# Power_Supply.net
KiCad netlist of a schematic drawn in Altium Designer
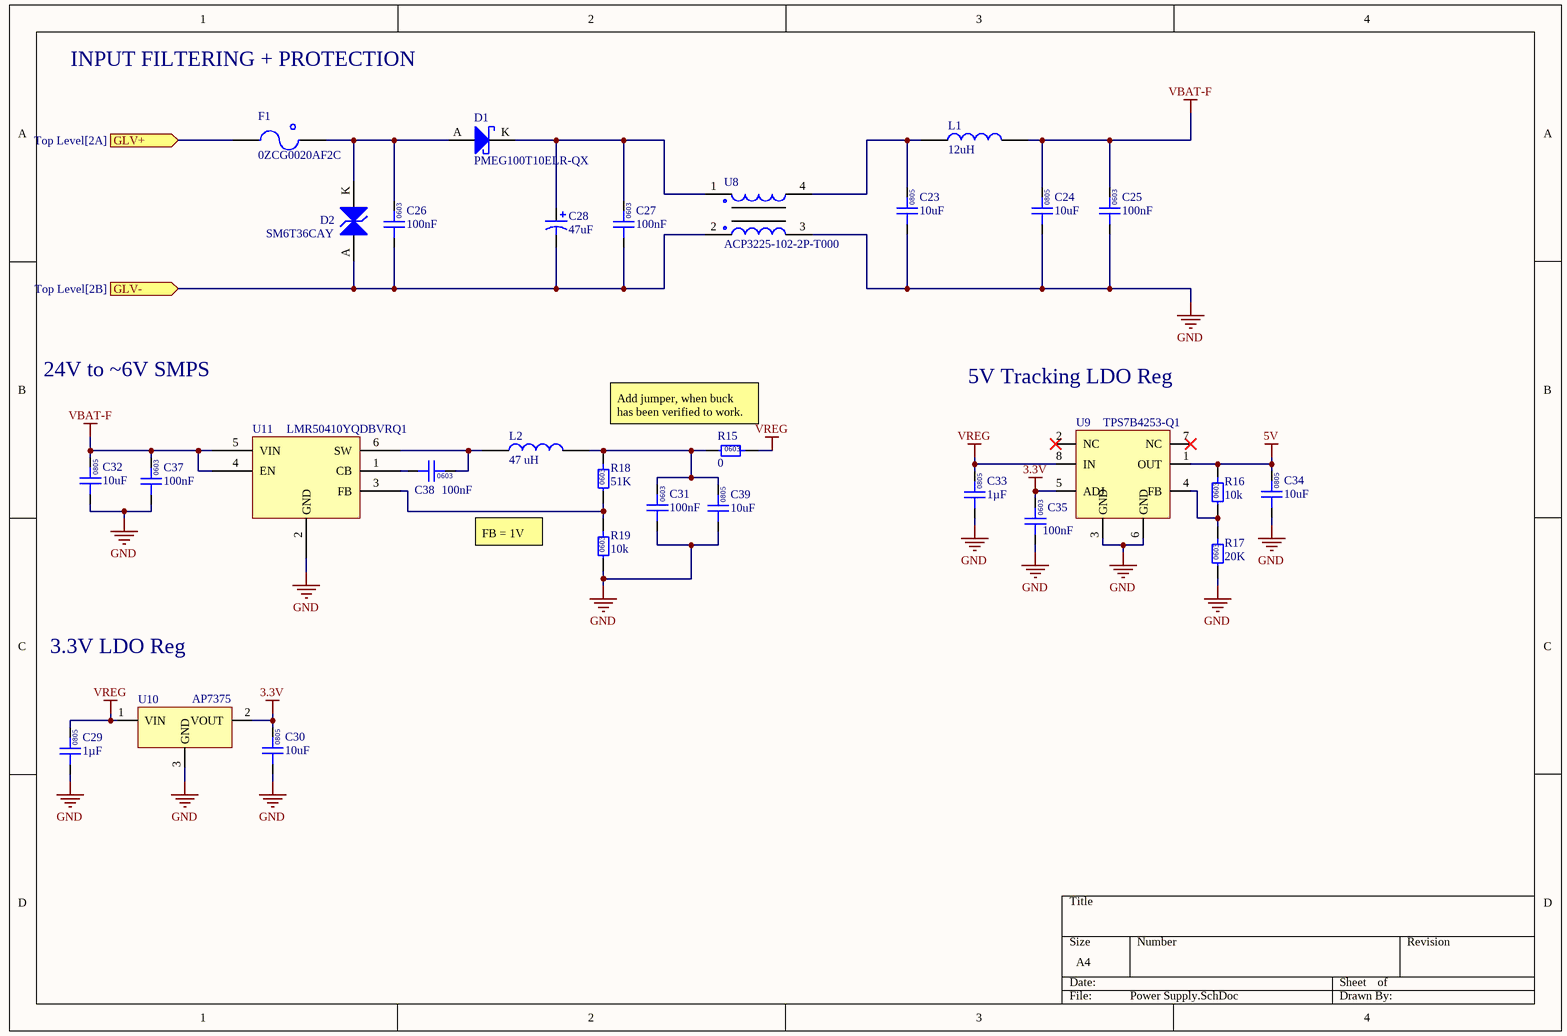
[diagram p0: Power Supply.SchDoc]

(export (version "E")
  (design (tool "Eeschema 10.0.6"))
  (components
    (comp (ref "C23")
      (value "10uF")
      (footprint "0805")
      (fields
        (field (name "PART NUMBER") "GRM21BR6YA106KE43L")
        (field (name "MANUFACTURER") "muRata")
        (field (name "TOLERANCE") "10%")
      )
      (libsource (lib "ts_standard_library") (part "Capacitor 0805"))
    )
    (comp (ref "C24")
      (value "10uF")
      (footprint "0805")
      (fields
        (field (name "PART NUMBER") "GRM21BR6YA106KE43L")
        (field (name "MANUFACTURER") "muRata")
        (field (name "TOLERANCE") "10%")
      )
      (libsource (lib "ts_standard_library") (part "Capacitor 0805"))
    )
    (comp (ref "C25")
      (value "100nF")
      (footprint "0603")
      (fields
        (field (name "PART NUMBER") "GCM188L81H104KA57D")
        (field (name "MANUFACTURER") "muRata")
        (field (name "TOLERANCE") "±10%")
      )
      (libsource (lib "ts_standard_library") (part "Capacitor 0603"))
    )
    (comp (ref "C26")
      (value "100nF")
      (footprint "0603")
      (fields
        (field (name "PART NUMBER") "GCM188L81H104KA57D")
        (field (name "MANUFACTURER") "muRata")
        (field (name "TOLERANCE") "±10%")
      )
      (libsource (lib "ts_standard_library") (part "Capacitor 0603"))
    )
    (comp (ref "C27")
      (value "100nF")
      (footprint "0603")
      (fields
        (field (name "PART NUMBER") "GCM188L81H104KA57D")
        (field (name "MANUFACTURER") "muRata")
        (field (name "TOLERANCE") "±10%")
      )
      (libsource (lib "ts_standard_library") (part "Capacitor 0603"))
    )
    (comp (ref "C28")
      (value "47uF")
      (footprint "CHEMI-CON ELCO")
      (fields (field (name "PART NUMBER") "HHXA350ARA470MF61G"))
      (libsource (lib "ts_standard_library") (part "Capacitor (Polarised)"))
    )
    (comp (ref "C29")
      (value "1µF")
      (footprint "0805")
      (fields
        (field (name "PART NUMBER") "GCM21BR71H105KA03L")
        (field (name "MANUFACTURER") "muRata")
        (field (name "TOLERANCE") "±10%")
      )
      (libsource (lib "ts_standard_library") (part "Capacitor 0805"))
    )
    (comp (ref "C30")
      (value "10uF")
      (footprint "0805")
      (fields
        (field (name "PART NUMBER") "GRM21BR6YA106KE43L")
        (field (name "MANUFACTURER") "muRata")
        (field (name "TOLERANCE") "10%")
      )
      (libsource (lib "ts_standard_library") (part "Capacitor 0805"))
    )
    (comp (ref "C31")
      (value "100nF")
      (footprint "0603")
      (fields
        (field (name "PART NUMBER") "GCM188L81H104KA57D")
        (field (name "MANUFACTURER") "muRata")
        (field (name "TOLERANCE") "±10%")
      )
      (libsource (lib "ts_standard_library") (part "Capacitor 0603"))
    )
    (comp (ref "C32")
      (value "10uF")
      (footprint "0805")
      (fields
        (field (name "PART NUMBER") "GRM21BR6YA106KE43L")
        (field (name "MANUFACTURER") "muRata")
        (field (name "TOLERANCE") "10%")
      )
      (libsource (lib "ts_standard_library") (part "Capacitor 0805"))
    )
    (comp (ref "C33")
      (value "1µF")
      (footprint "0805")
      (fields
        (field (name "PART NUMBER") "GCM21BR71H105KA03L")
        (field (name "MANUFACTURER") "muRata")
        (field (name "TOLERANCE") "±10%")
      )
      (libsource (lib "ts_standard_library") (part "Capacitor 0805"))
    )
    (comp (ref "C34")
      (value "10uF")
      (footprint "0805")
      (fields
        (field (name "PART NUMBER") "GRM21BR6YA106KE43L")
        (field (name "MANUFACTURER") "muRata")
        (field (name "TOLERANCE") "10%")
      )
      (libsource (lib "ts_standard_library") (part "Capacitor 0805"))
    )
    (comp (ref "C35")
      (value "100nF")
      (footprint "0603")
      (fields
        (field (name "PART NUMBER") "GCM188L81H104KA57D")
        (field (name "MANUFACTURER") "muRata")
        (field (name "TOLERANCE") "±10%")
      )
      (libsource (lib "ts_standard_library") (part "Capacitor 0603"))
    )
    (comp (ref "C37")
      (value "100nF")
      (footprint "0603")
      (fields
        (field (name "PART NUMBER") "GCM188L81H104KA57D")
        (field (name "MANUFACTURER") "muRata")
        (field (name "TOLERANCE") "±10%")
      )
      (libsource (lib "ts_standard_library") (part "Capacitor 0603"))
    )
    (comp (ref "C38")
      (value "100nF")
      (footprint "0603")
      (fields
        (field (name "PART NUMBER") "GCM188L81H104KA57D")
        (field (name "MANUFACTURER") "muRata")
        (field (name "TOLERANCE") "±10%")
      )
      (libsource (lib "ts_standard_library") (part "Capacitor 0603"))
    )
    (comp (ref "C39")
      (value "10uF")
      (footprint "0805")
      (fields
        (field (name "PART NUMBER") "GRM21BR6YA106KE43L")
        (field (name "MANUFACTURER") "muRata")
        (field (name "TOLERANCE") "10%")
      )
      (libsource (lib "ts_standard_library") (part "Capacitor 0805"))
    )
    (comp (ref "D1")
      (value "PMEG100T10ELR-QX")
      (footprint "NXP SOD123W")
      (fields
        (field (name "MANUFACTURER") "Nexperia USA Inc.")
        (field (name "DIGIKEY PART NUMBER") "1727-PMEG100T10ELR-QXCT-ND")
      )
      (libsource (lib "ts_standard_library") (part "Diode (Schottky)"))
    )
    (comp (ref "D2")
      (value "SM6T36CAY")
      (footprint "ST SMB DIODE")
      (fields
        (field (name "MANUFACTURER") "STMicroelectronics")
        (field (name "DIGIKEY PART NUMBER") "497-10804-1-ND")
      )
      (libsource (lib "ts_standard_library") (part "TVS (Bidirectional)"))
    )
    (comp (ref "F1")
      (value "0ZCG0020AF2C")
      (footprint "1812 (PPTC FUSE)")
      (description "PTC RESET FUSE 60V 200MA 1812")
      (fields
        (field (name "MANUFACTURER") "Bel Fuse Inc.")
        (field (name "DIGIKEY PART NUMBER") "507-1757-1-ND")
      )
      (libsource (lib "ts_standard_library") (part "PTC Fuse"))
    )
    (comp (ref "L1")
      (value "12uH")
      (footprint "1812")
      (fields
        (field (name "PART NUMBER") "RLS-126")
        (field (name "MANUFACTURER") "Recom")
        (field (name "TOLERANCE") "0.2")
      )
      (libsource (lib "ts_standard_library") (part "Inductor"))
    )
    (comp (ref "L2")
      (value "47 uH")
      (footprint "SRN8040TA")
      (fields
        (field (name "PART NUMBER") "SRN8040TA-470M")
        (field (name "MANUFACTURER") "Bourns")
        (field (name "TOLERANCE") "0.2")
      )
      (libsource (lib "ts_standard_library") (part "Inductor"))
    )
    (comp (ref "R15")
      (value "0")
      (footprint "0603")
      (fields
        (field (name "PART NUMBER") "RC0603JR-070RL")
        (field (name "MANUFACTURER") "YAGEO")
        (field (name "TOLERANCE") "0.01")
      )
      (libsource (lib "ts_standard_library") (part "Resistor 0603"))
    )
    (comp (ref "R16")
      (value "10k")
      (footprint "0603")
      (fields
        (field (name "PART NUMBER") "RC0603FR-0710KL")
        (field (name "MANUFACTURER") "YAGEO")
        (field (name "TOLERANCE") "0.01")
      )
      (libsource (lib "ts_standard_library") (part "Resistor 0603"))
    )
    (comp (ref "R17")
      (value "20K")
      (footprint "0603")
      (fields
        (field (name "PART NUMBER") "RC0603FR-0720KL")
        (field (name "MANUFACTURER") "YAGEO")
        (field (name "TOLERANCE") "0.01")
      )
      (libsource (lib "ts_standard_library") (part "Resistor 0603"))
    )
    (comp (ref "R18")
      (value "51K")
      (footprint "0603")
      (fields
        (field (name "PART NUMBER") "RC0603JR-0751KL")
        (field (name "MANUFACTURER") "YAGEO")
        (field (name "TOLERANCE") "0.01")
      )
      (libsource (lib "ts_standard_library") (part "Resistor 0603"))
    )
    (comp (ref "R19")
      (value "10k")
      (footprint "0603")
      (fields
        (field (name "PART NUMBER") "RC0603FR-0710KL")
        (field (name "MANUFACTURER") "YAGEO")
        (field (name "TOLERANCE") "0.01")
      )
      (libsource (lib "ts_standard_library") (part "Resistor 0603"))
    )
    (comp (ref "U8")
      (value "ACP3225-102-2P-T000")
      (footprint "ACP3225")
      (fields
        (field (name "MANUFACTURER") "TDK Corporation")
        (field (name "TOLERANCE") "0.25")
        (field (name "DIGIKEY PART NUMBER") "445-8637-1-ND")
      )
      (libsource (lib "ts_standard_library") (part "CM Choke 2"))
    )
    (comp (ref "U9")
      (value "TPS7B4253-Q1")
      (footprint "TI 8-PowerSOIC")
      (description "IC REG LIN POS ADJ 300MA 8SO")
      (fields
        (field (name "MANUFACTURER") "Texas Instruments")
        (field (name "DIGIKEY PART NUMBER") "296-43781-1-ND")
      )
      (libsource (lib "ts_standard_library") (part "TPS7B4253-Q1"))
    )
    (comp (ref "U10")
      (value "AP7375")
      (footprint "DI SOT-23-3")
      (description "IC REG LIN 3.3V 300MA SOT23-3")
      (fields
        (field (name "PART NUMBER") "AP7375-33SA-7")
        (field (name "MANUFACTURER") "Diodes Incorporated")
      )
      (libsource (lib "ts_standard_library") (part "AP7375"))
    )
    (comp (ref "U11")
      (value "LMR50410YQDBVRQ1")
      (footprint "TI SOT-23-6")
      (description "IC REG BUCK ADJ 1A SOT23-6")
      (fields
        (field (name "MANUFACTURER") "Texas Instruments")
        (field (name "DIGIKEY PART NUMBER") "296-LMR50410YQDBVRQ1CT-ND")
      )
      (libsource (lib "ts_standard_library") (part "LMR50410-Q1"))
    )
  )
  (nets
    (net (code "1") (name "/GLV+") (class "Default")
      (node (ref "F1") (pin "1") (pinfunction "1_1") (pintype "passive"))
    )
    (net (code "2") (name "/GLV-") (class "Default")
      (node (ref "C26") (pin "1") (pinfunction "1_1") (pintype "passive"))
      (node (ref "C27") (pin "1") (pinfunction "1_1") (pintype "passive"))
      (node (ref "C28") (pin "1") (pinfunction "1_1") (pintype "passive"))
      (node (ref "D2") (pin "A") (pinfunction "A_A") (pintype "passive"))
      (node (ref "U8") (pin "2") (pinfunction "2_2") (pintype "passive"))
    )
    (net (code "3") (name "3.3V") (class "Default")
      (node (ref "C30") (pin "2") (pinfunction "2_2") (pintype "passive"))
      (node (ref "C35") (pin "2") (pinfunction "2_2") (pintype "passive"))
      (node (ref "U10") (pin "2") (pinfunction "VOUT_2") (pintype "passive"))
      (node (ref "U9") (pin "5") (pinfunction "ADJ_5") (pintype "passive"))
    )
    (net (code "4") (name "5V") (class "Default")
      (node (ref "C34") (pin "2") (pinfunction "2_2") (pintype "passive"))
      (node (ref "R16") (pin "2") (pinfunction "2_2") (pintype "passive"))
      (node (ref "U9") (pin "1") (pinfunction "OUT_1") (pintype "passive"))
    )
    (net (code "5") (name "GND") (class "Default")
      (node (ref "C23") (pin "1") (pinfunction "1_1") (pintype "passive"))
      (node (ref "C24") (pin "1") (pinfunction "1_1") (pintype "passive"))
      (node (ref "C25") (pin "1") (pinfunction "1_1") (pintype "passive"))
      (node (ref "C29") (pin "1") (pinfunction "1_1") (pintype "passive"))
      (node (ref "C30") (pin "1") (pinfunction "1_1") (pintype "passive"))
      (node (ref "C31") (pin "1") (pinfunction "1_1") (pintype "passive"))
      (node (ref "C32") (pin "1") (pinfunction "1_1") (pintype "passive"))
      (node (ref "C33") (pin "1") (pinfunction "1_1") (pintype "passive"))
      (node (ref "C34") (pin "1") (pinfunction "1_1") (pintype "passive"))
      (node (ref "C35") (pin "1") (pinfunction "1_1") (pintype "passive"))
      (node (ref "C37") (pin "1") (pinfunction "1_1") (pintype "passive"))
      (node (ref "C39") (pin "1") (pinfunction "1_1") (pintype "passive"))
      (node (ref "R17") (pin "1") (pinfunction "1_1") (pintype "passive"))
      (node (ref "R19") (pin "1") (pinfunction "1_1") (pintype "passive"))
      (node (ref "U10") (pin "3") (pinfunction "GND_3") (pintype "passive"))
      (node (ref "U11") (pin "2") (pinfunction "GND_2") (pintype "passive"))
      (node (ref "U8") (pin "3") (pinfunction "3_3") (pintype "power_in"))
      (node (ref "U9") (pin "3") (pinfunction "GND_3") (pintype "passive"))
      (node (ref "U9") (pin "6") (pinfunction "GND_6") (pintype "passive"))
    )
    (net (code "6") (name "Net-(C23-Pad2)") (class "Default")
      (node (ref "C23") (pin "2") (pinfunction "2_2") (pintype "passive"))
      (node (ref "L1") (pin "2") (pinfunction "2_2") (pintype "passive"))
      (node (ref "U8") (pin "4") (pinfunction "4_4") (pintype "passive"))
    )
    (net (code "7") (name "Net-(C26-Pad2)") (class "Default")
      (node (ref "C26") (pin "2") (pinfunction "2_2") (pintype "passive"))
      (node (ref "D1") (pin "A") (pinfunction "A_A") (pintype "passive"))
      (node (ref "D2") (pin "K") (pinfunction "K_K") (pintype "passive"))
      (node (ref "F1") (pin "2") (pinfunction "2_2") (pintype "passive"))
    )
    (net (code "8") (name "Net-(C27-Pad2)") (class "Default")
      (node (ref "C27") (pin "2") (pinfunction "2_2") (pintype "passive"))
      (node (ref "C28") (pin "2") (pinfunction "2_2") (pintype "passive"))
      (node (ref "D1") (pin "K") (pinfunction "K_K") (pintype "passive"))
      (node (ref "U8") (pin "1") (pinfunction "1_1") (pintype "passive"))
    )
    (net (code "9") (name "Net-(C31-Pad2)") (class "Default")
      (node (ref "C31") (pin "2") (pinfunction "2_2") (pintype "passive"))
      (node (ref "C39") (pin "2") (pinfunction "2_2") (pintype "passive"))
      (node (ref "L2") (pin "1") (pinfunction "1_1") (pintype "passive"))
      (node (ref "R15") (pin "1") (pinfunction "1_1") (pintype "passive"))
      (node (ref "R18") (pin "2") (pinfunction "2_2") (pintype "passive"))
    )
    (net (code "10") (name "Net-(U9-FB)") (class "Default")
      (node (ref "R16") (pin "1") (pinfunction "1_1") (pintype "passive"))
      (node (ref "R17") (pin "2") (pinfunction "2_2") (pintype "passive"))
      (node (ref "U9") (pin "4") (pinfunction "FB_4") (pintype "passive"))
    )
    (net (code "11") (name "Net-(U11-CB)") (class "Default")
      (node (ref "C38") (pin "1") (pinfunction "1_1") (pintype "passive"))
      (node (ref "U11") (pin "1") (pinfunction "CB_1") (pintype "passive"))
    )
    (net (code "12") (name "Net-(U11-FB)") (class "Default")
      (node (ref "R18") (pin "1") (pinfunction "1_1") (pintype "passive"))
      (node (ref "R19") (pin "2") (pinfunction "2_2") (pintype "passive"))
      (node (ref "U11") (pin "3") (pinfunction "FB_3") (pintype "passive"))
    )
    (net (code "13") (name "Net-(U11-SW)") (class "Default")
      (node (ref "C38") (pin "2") (pinfunction "2_2") (pintype "passive"))
      (node (ref "L2") (pin "2") (pinfunction "2_2") (pintype "passive"))
      (node (ref "U11") (pin "6") (pinfunction "SW_6") (pintype "passive"))
    )
    (net (code "14") (name "VBAT-F") (class "Default")
      (node (ref "C24") (pin "2") (pinfunction "2_2") (pintype "passive"))
      (node (ref "C25") (pin "2") (pinfunction "2_2") (pintype "passive"))
      (node (ref "C32") (pin "2") (pinfunction "2_2") (pintype "passive"))
      (node (ref "C37") (pin "2") (pinfunction "2_2") (pintype "passive"))
      (node (ref "L1") (pin "1") (pinfunction "1_1") (pintype "passive"))
      (node (ref "U11") (pin "4") (pinfunction "EN_4") (pintype "passive"))
      (node (ref "U11") (pin "5") (pinfunction "VIN_5") (pintype "passive"))
    )
    (net (code "15") (name "VREG") (class "Default")
      (node (ref "C29") (pin "2") (pinfunction "2_2") (pintype "passive"))
      (node (ref "C33") (pin "2") (pinfunction "2_2") (pintype "passive"))
      (node (ref "R15") (pin "2") (pinfunction "2_2") (pintype "passive"))
      (node (ref "U10") (pin "1") (pinfunction "VIN_1") (pintype "passive"))
      (node (ref "U9") (pin "8") (pinfunction "IN_8") (pintype "passive"))
    )
    (net (code "16") (name "unconnected-(U9-NC-Pad2)") (class "Default")
      (node (ref "U9") (pin "2") (pinfunction "NC_2") (pintype "passive+no_connect"))
    )
    (net (code "17") (name "unconnected-(U9-NC-Pad7)") (class "Default")
      (node (ref "U9") (pin "7") (pinfunction "NC_7") (pintype "passive+no_connect"))
    )
  )
)
